# Sheet1.net
KiCad netlist of a schematic drawn in Altium Designer
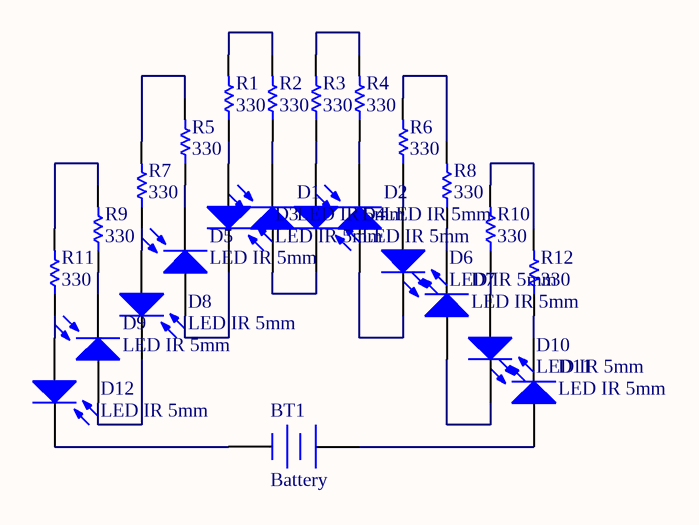
[diagram p0: Sheet1.SchDoc]

(export (version "E")
  (design (tool "Eeschema 10.0.6"))
  (components
    (comp (ref "BT1")
      (value "Battery")
      (footprint "BAT-2")
      (description "Multicell Battery")
      (fields (field (name "PUBLISHER") "Altium Limited"))
      (libsource (lib "Miscellaneous Devices") (part "Battery"))
    )
    (comp (ref "D1")
      (value "LED IR 5mm")
      (footprint "LED-1")
      (description "Typical LED")
      (fields (field (name "DESIGNER") "Seyed Mohsen Ghasemian") (field (name "PUBLISHER") "www.picpars.com"))
      (libsource (lib "PicPars.com_usefully_Library") (part "LED IR 5mm"))
    )
    (comp (ref "D2")
      (value "LED IR 5mm")
      (footprint "LED-1")
      (description "Typical LED")
      (fields (field (name "DESIGNER") "Seyed Mohsen Ghasemian") (field (name "PUBLISHER") "www.picpars.com"))
      (libsource (lib "PicPars.com_usefully_Library") (part "LED IR 5mm"))
    )
    (comp (ref "D3")
      (value "LED IR 5mm")
      (footprint "LED-1")
      (description "Typical LED")
      (fields (field (name "DESIGNER") "Seyed Mohsen Ghasemian") (field (name "PUBLISHER") "www.picpars.com"))
      (libsource (lib "PicPars.com_usefully_Library") (part "LED IR 5mm"))
    )
    (comp (ref "D4")
      (value "LED IR 5mm")
      (footprint "LED-1")
      (description "Typical LED")
      (fields (field (name "DESIGNER") "Seyed Mohsen Ghasemian") (field (name "PUBLISHER") "www.picpars.com"))
      (libsource (lib "PicPars.com_usefully_Library") (part "LED IR 5mm"))
    )
    (comp (ref "D5")
      (value "LED IR 5mm")
      (footprint "LED-1")
      (description "Typical LED")
      (fields (field (name "DESIGNER") "Seyed Mohsen Ghasemian") (field (name "PUBLISHER") "www.picpars.com"))
      (libsource (lib "PicPars.com_usefully_Library") (part "LED IR 5mm"))
    )
    (comp (ref "D6")
      (value "LED IR 5mm")
      (footprint "LED-1")
      (description "Typical LED")
      (fields (field (name "DESIGNER") "Seyed Mohsen Ghasemian") (field (name "PUBLISHER") "www.picpars.com"))
      (libsource (lib "PicPars.com_usefully_Library") (part "LED IR 5mm"))
    )
    (comp (ref "D7")
      (value "LED IR 5mm")
      (footprint "LED-1")
      (description "Typical LED")
      (fields (field (name "DESIGNER") "Seyed Mohsen Ghasemian") (field (name "PUBLISHER") "www.picpars.com"))
      (libsource (lib "PicPars.com_usefully_Library") (part "LED IR 5mm"))
    )
    (comp (ref "D8")
      (value "LED IR 5mm")
      (footprint "LED-1")
      (description "Typical LED")
      (fields (field (name "DESIGNER") "Seyed Mohsen Ghasemian") (field (name "PUBLISHER") "www.picpars.com"))
      (libsource (lib "PicPars.com_usefully_Library") (part "LED IR 5mm"))
    )
    (comp (ref "D9")
      (value "LED IR 5mm")
      (footprint "LED-1")
      (description "Typical LED")
      (fields (field (name "DESIGNER") "Seyed Mohsen Ghasemian") (field (name "PUBLISHER") "www.picpars.com"))
      (libsource (lib "PicPars.com_usefully_Library") (part "LED IR 5mm"))
    )
    (comp (ref "D10")
      (value "LED IR 5mm")
      (footprint "LED-1")
      (description "Typical LED")
      (fields (field (name "DESIGNER") "Seyed Mohsen Ghasemian") (field (name "PUBLISHER") "www.picpars.com"))
      (libsource (lib "PicPars.com_usefully_Library") (part "LED IR 5mm"))
    )
    (comp (ref "D11")
      (value "LED IR 5mm")
      (footprint "LED-1")
      (description "Typical LED")
      (fields (field (name "DESIGNER") "Seyed Mohsen Ghasemian") (field (name "PUBLISHER") "www.picpars.com"))
      (libsource (lib "PicPars.com_usefully_Library") (part "LED IR 5mm"))
    )
    (comp (ref "D12")
      (value "LED IR 5mm")
      (footprint "LED-1")
      (description "Typical LED")
      (fields (field (name "DESIGNER") "Seyed Mohsen Ghasemian") (field (name "PUBLISHER") "www.picpars.com"))
      (libsource (lib "PicPars.com_usefully_Library") (part "LED IR 5mm"))
    )
    (comp (ref "R1")
      (value "330")
      (footprint "Res50")
      (description "Resistor 0.5")
      (fields
        (field (name "Comment") "Resistor vertical")
        (field (name "PUBLISHER") "Seyed mohsen ghasemian")
      )
      (libsource (lib "PicPars.com_usefully_Library") (part "Resistor vertical"))
    )
    (comp (ref "R2")
      (value "330")
      (footprint "Res50")
      (description "Resistor 0.5")
      (fields
        (field (name "Comment") "Resistor vertical")
        (field (name "PUBLISHER") "Seyed mohsen ghasemian")
      )
      (libsource (lib "PicPars.com_usefully_Library") (part "Resistor vertical"))
    )
    (comp (ref "R3")
      (value "330")
      (footprint "Res50")
      (description "Resistor 0.5")
      (fields
        (field (name "Comment") "Resistor vertical")
        (field (name "PUBLISHER") "Seyed mohsen ghasemian")
      )
      (libsource (lib "PicPars.com_usefully_Library") (part "Resistor vertical"))
    )
    (comp (ref "R4")
      (value "330")
      (footprint "Res50")
      (description "Resistor 0.5")
      (fields
        (field (name "Comment") "Resistor vertical")
        (field (name "PUBLISHER") "Seyed mohsen ghasemian")
      )
      (libsource (lib "PicPars.com_usefully_Library") (part "Resistor vertical"))
    )
    (comp (ref "R5")
      (value "330")
      (footprint "Res50")
      (description "Resistor 0.5")
      (fields
        (field (name "Comment") "Resistor vertical")
        (field (name "PUBLISHER") "Seyed mohsen ghasemian")
      )
      (libsource (lib "PicPars.com_usefully_Library") (part "Resistor vertical"))
    )
    (comp (ref "R6")
      (value "330")
      (footprint "Res50")
      (description "Resistor 0.5")
      (fields
        (field (name "Comment") "Resistor vertical")
        (field (name "PUBLISHER") "Seyed mohsen ghasemian")
      )
      (libsource (lib "PicPars.com_usefully_Library") (part "Resistor vertical"))
    )
    (comp (ref "R7")
      (value "330")
      (footprint "Res50")
      (description "Resistor 0.5")
      (fields
        (field (name "Comment") "Resistor vertical")
        (field (name "PUBLISHER") "Seyed mohsen ghasemian")
      )
      (libsource (lib "PicPars.com_usefully_Library") (part "Resistor vertical"))
    )
    (comp (ref "R8")
      (value "330")
      (footprint "Res50")
      (description "Resistor 0.5")
      (fields
        (field (name "Comment") "Resistor vertical")
        (field (name "PUBLISHER") "Seyed mohsen ghasemian")
      )
      (libsource (lib "PicPars.com_usefully_Library") (part "Resistor vertical"))
    )
    (comp (ref "R9")
      (value "330")
      (footprint "Res50")
      (description "Resistor 0.5")
      (fields
        (field (name "Comment") "Resistor vertical")
        (field (name "PUBLISHER") "Seyed mohsen ghasemian")
      )
      (libsource (lib "PicPars.com_usefully_Library") (part "Resistor vertical"))
    )
    (comp (ref "R10")
      (value "330")
      (footprint "Res50")
      (description "Resistor 0.5")
      (fields
        (field (name "Comment") "Resistor vertical")
        (field (name "PUBLISHER") "Seyed mohsen ghasemian")
      )
      (libsource (lib "PicPars.com_usefully_Library") (part "Resistor vertical"))
    )
    (comp (ref "R11")
      (value "330")
      (footprint "Res50")
      (description "Resistor 0.5")
      (fields
        (field (name "Comment") "Resistor vertical")
        (field (name "PUBLISHER") "Seyed mohsen ghasemian")
      )
      (libsource (lib "PicPars.com_usefully_Library") (part "Resistor vertical"))
    )
    (comp (ref "R12")
      (value "330")
      (footprint "Res50")
      (description "Resistor 0.5")
      (fields
        (field (name "Comment") "Resistor vertical")
        (field (name "PUBLISHER") "Seyed mohsen ghasemian")
      )
      (libsource (lib "PicPars.com_usefully_Library") (part "Resistor vertical"))
    )
  )
  (nets
    (net (code "1") (name "Net-(BT1-+)") (class "Default")
      (node (ref "BT1") (pin "1") (pinfunction "+_1") (pintype "passive"))
      (node (ref "D11") (pin "1") (pinfunction "A_1") (pintype "passive"))
    )
    (net (code "2") (name "Net-(BT1--)") (class "Default")
      (node (ref "BT1") (pin "2") (pinfunction "-_2") (pintype "passive"))
      (node (ref "D12") (pin "2") (pinfunction "K_2") (pintype "passive"))
    )
    (net (code "3") (name "Net-(D1-A)") (class "Default")
      (node (ref "D1") (pin "1") (pinfunction "A_1") (pintype "passive"))
      (node (ref "D4") (pin "2") (pinfunction "K_2") (pintype "passive"))
    )
    (net (code "4") (name "Net-(D1-K)") (class "Default")
      (node (ref "D1") (pin "2") (pinfunction "K_2") (pintype "passive"))
      (node (ref "R2") (pin "1") (pinfunction "1_1") (pintype "passive"))
    )
    (net (code "5") (name "Net-(D2-A)") (class "Default")
      (node (ref "D2") (pin "1") (pinfunction "A_1") (pintype "passive"))
      (node (ref "D6") (pin "2") (pinfunction "K_2") (pintype "passive"))
    )
    (net (code "6") (name "Net-(D2-K)") (class "Default")
      (node (ref "D2") (pin "2") (pinfunction "K_2") (pintype "passive"))
      (node (ref "R4") (pin "1") (pinfunction "1_1") (pintype "passive"))
    )
    (net (code "7") (name "Net-(D3-A)") (class "Default")
      (node (ref "D3") (pin "1") (pinfunction "A_1") (pintype "passive"))
      (node (ref "R1") (pin "1") (pinfunction "1_1") (pintype "passive"))
    )
    (net (code "8") (name "Net-(D3-K)") (class "Default")
      (node (ref "D3") (pin "2") (pinfunction "K_2") (pintype "passive"))
      (node (ref "D5") (pin "1") (pinfunction "A_1") (pintype "passive"))
    )
    (net (code "9") (name "Net-(D4-A)") (class "Default")
      (node (ref "D4") (pin "1") (pinfunction "A_1") (pintype "passive"))
      (node (ref "R3") (pin "1") (pinfunction "1_1") (pintype "passive"))
    )
    (net (code "10") (name "Net-(D5-K)") (class "Default")
      (node (ref "D5") (pin "2") (pinfunction "K_2") (pintype "passive"))
      (node (ref "R5") (pin "1") (pinfunction "1_1") (pintype "passive"))
    )
    (net (code "11") (name "Net-(D6-A)") (class "Default")
      (node (ref "D6") (pin "1") (pinfunction "A_1") (pintype "passive"))
      (node (ref "R6") (pin "1") (pinfunction "1_1") (pintype "passive"))
    )
    (net (code "12") (name "Net-(D7-K)") (class "Default")
      (node (ref "D7") (pin "2") (pinfunction "K_2") (pintype "passive"))
      (node (ref "R8") (pin "1") (pinfunction "1_1") (pintype "passive"))
    )
    (net (code "13") (name "Net-(D8-A)") (class "Default")
      (node (ref "D8") (pin "1") (pinfunction "A_1") (pintype "passive"))
      (node (ref "R7") (pin "1") (pinfunction "1_1") (pintype "passive"))
    )
    (net (code "14") (name "Net-(D8-K)") (class "Default")
      (node (ref "D8") (pin "2") (pinfunction "K_2") (pintype "passive"))
      (node (ref "D9") (pin "1") (pinfunction "A_1") (pintype "passive"))
    )
    (net (code "15") (name "Net-(D9-K)") (class "Default")
      (node (ref "D9") (pin "2") (pinfunction "K_2") (pintype "passive"))
      (node (ref "R9") (pin "1") (pinfunction "1_1") (pintype "passive"))
    )
    (net (code "16") (name "Net-(D10-A)") (class "Default")
      (node (ref "D10") (pin "1") (pinfunction "A_1") (pintype "passive"))
      (node (ref "R10") (pin "1") (pinfunction "1_1") (pintype "passive"))
    )
    (net (code "17") (name "Net-(D10-K)") (class "Default")
      (node (ref "D10") (pin "2") (pinfunction "K_2") (pintype "passive"))
      (node (ref "D7") (pin "1") (pinfunction "A_1") (pintype "passive"))
    )
    (net (code "18") (name "Net-(D11-K)") (class "Default")
      (node (ref "D11") (pin "2") (pinfunction "K_2") (pintype "passive"))
      (node (ref "R12") (pin "1") (pinfunction "1_1") (pintype "passive"))
    )
    (net (code "19") (name "Net-(D12-A)") (class "Default")
      (node (ref "D12") (pin "1") (pinfunction "A_1") (pintype "passive"))
      (node (ref "R11") (pin "1") (pinfunction "1_1") (pintype "passive"))
    )
    (net (code "20") (name "Net-(R1-Pad2)") (class "Default")
      (node (ref "R1") (pin "2") (pinfunction "2_2") (pintype "passive"))
      (node (ref "R2") (pin "2") (pinfunction "2_2") (pintype "passive"))
    )
    (net (code "21") (name "Net-(R3-Pad2)") (class "Default")
      (node (ref "R3") (pin "2") (pinfunction "2_2") (pintype "passive"))
      (node (ref "R4") (pin "2") (pinfunction "2_2") (pintype "passive"))
    )
    (net (code "22") (name "Net-(R5-Pad2)") (class "Default")
      (node (ref "R5") (pin "2") (pinfunction "2_2") (pintype "passive"))
      (node (ref "R7") (pin "2") (pinfunction "2_2") (pintype "passive"))
    )
    (net (code "23") (name "Net-(R6-Pad2)") (class "Default")
      (node (ref "R6") (pin "2") (pinfunction "2_2") (pintype "passive"))
      (node (ref "R8") (pin "2") (pinfunction "2_2") (pintype "passive"))
    )
    (net (code "24") (name "Net-(R10-Pad2)") (class "Default")
      (node (ref "R10") (pin "2") (pinfunction "2_2") (pintype "passive"))
      (node (ref "R12") (pin "2") (pinfunction "2_2") (pintype "passive"))
    )
    (net (code "25") (name "Net-(R11-Pad2)") (class "Default")
      (node (ref "R11") (pin "2") (pinfunction "2_2") (pintype "passive"))
      (node (ref "R9") (pin "2") (pinfunction "2_2") (pintype "passive"))
    )
  )
)
